# music-thing.net
KiCad netlist of a schematic drawn in EAGLE
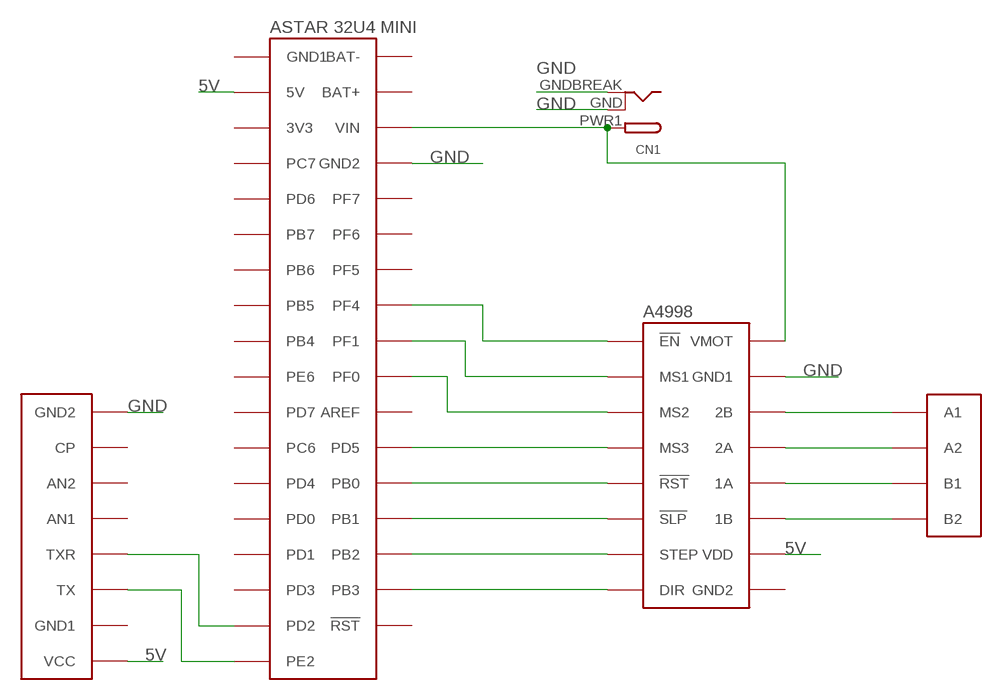
[diagram p0: schematic, sheet 1]

(export (version "E")
  (design (tool "Eeschema 10.0.6"))
  (components
    (comp (ref "CN1")
      (value "DCBARRELSMT")
      (footprint "eagle-import:DCJACK_2MM_SMT")
      (libsource (lib "eagle-import") (part "DCBARRELSMT"))
    )
    (comp (ref "U$1")
      (value "A4998")
      (footprint "eagle-import:A4998")
      (libsource (lib "eagle-import") (part "A4998"))
    )
    (comp (ref "U$2")
      (value "ASTAR32U4MINI")
      (footprint "eagle-import:ASTAR32U4MINI")
      (libsource (lib "eagle-import") (part "ASTAR32U4MINI"))
    )
    (comp (ref "U$3")
      (value "CON-USB-READER-V18")
      (footprint "eagle-import:CON-USB-READER-V18")
      (libsource (lib "eagle-import") (part "CON-USB-READER-V18"))
    )
    (comp (ref "U$4")
      (value "CON-MOTOR")
      (footprint "eagle-import:CON-MOTOR")
      (libsource (lib "eagle-import") (part "CON-MOTOR"))
    )
  )
  (nets
    (net (code "1") (name "/5V") (class "Default")
      (node (ref "U$1") (pin "VDD") (pinfunction "VDD_VDD") (pintype "bidirectional"))
      (node (ref "U$2") (pin "5V") (pinfunction "5V_5V") (pintype "bidirectional"))
      (node (ref "U$3") (pin "VCC") (pinfunction "VCC_VCC") (pintype "bidirectional"))
    )
    (net (code "2") (name "/GND") (class "Default")
      (node (ref "CN1") (pin "GND") (pinfunction "GNDBREAK_GND") (pintype "power_in"))
      (node (ref "CN1") (pin "GNDBREAK") (pinfunction "GND_GNDBREAK") (pintype "power_in"))
      (node (ref "U$1") (pin "GND1") (pinfunction "GND1_GND1") (pintype "bidirectional"))
      (node (ref "U$2") (pin "GND2") (pinfunction "GND2_GND2") (pintype "bidirectional"))
      (node (ref "U$3") (pin "GND2") (pinfunction "GND2_GND2") (pintype "bidirectional"))
    )
    (net (code "3") (name "Net-(CN1-PWR)") (class "Default")
      (node (ref "CN1") (pin "PWR1") (pinfunction "PWR_PWR1") (pintype "power_in"))
      (node (ref "U$1") (pin "VMOT") (pinfunction "VMOT_VMOT") (pintype "bidirectional"))
      (node (ref "U$2") (pin "VIN") (pinfunction "VIN_VIN") (pintype "bidirectional"))
    )
    (net (code "4") (name "Net-(U$1-Pad1A)") (class "Default")
      (node (ref "U$1") (pin "1A") (pinfunction "1A_1A") (pintype "bidirectional"))
      (node (ref "U$4") (pin "B1") (pinfunction "B1_B1") (pintype "bidirectional"))
    )
    (net (code "5") (name "Net-(U$1-Pad1B)") (class "Default")
      (node (ref "U$1") (pin "1B") (pinfunction "1B_1B") (pintype "bidirectional"))
      (node (ref "U$4") (pin "B2") (pinfunction "B2_B2") (pintype "bidirectional"))
    )
    (net (code "6") (name "Net-(U$1-Pad2A)") (class "Default")
      (node (ref "U$1") (pin "2A") (pinfunction "2A_2A") (pintype "bidirectional"))
      (node (ref "U$4") (pin "A2") (pinfunction "A2_A2") (pintype "bidirectional"))
    )
    (net (code "7") (name "Net-(U$1-Pad2B)") (class "Default")
      (node (ref "U$1") (pin "2B") (pinfunction "2B_2B") (pintype "bidirectional"))
      (node (ref "U$4") (pin "A1") (pinfunction "A1_A1") (pintype "bidirectional"))
    )
    (net (code "8") (name "Net-(U$1-PadDIR)") (class "Default")
      (node (ref "U$1") (pin "DIR") (pinfunction "DIR_DIR") (pintype "bidirectional"))
      (node (ref "U$2") (pin "PB3") (pinfunction "PB3_PB3") (pintype "bidirectional"))
    )
    (net (code "9") (name "Net-(U$1-PadMS1)") (class "Default")
      (node (ref "U$1") (pin "MS1") (pinfunction "MS1_MS1") (pintype "bidirectional"))
      (node (ref "U$2") (pin "PF1") (pinfunction "PF1_PF1") (pintype "bidirectional"))
    )
    (net (code "10") (name "Net-(U$1-PadMS2)") (class "Default")
      (node (ref "U$1") (pin "MS2") (pinfunction "MS2_MS2") (pintype "bidirectional"))
      (node (ref "U$2") (pin "PF0") (pinfunction "PF0_PF0") (pintype "bidirectional"))
    )
    (net (code "11") (name "Net-(U$1-PadMS3)") (class "Default")
      (node (ref "U$1") (pin "MS3") (pinfunction "MS3_MS3") (pintype "bidirectional"))
      (node (ref "U$2") (pin "PD5") (pinfunction "PD5_PD5") (pintype "bidirectional"))
    )
    (net (code "12") (name "Net-(U$1-STEP)") (class "Default")
      (node (ref "U$1") (pin "STP") (pinfunction "STEP_STP") (pintype "bidirectional"))
      (node (ref "U$2") (pin "PB2") (pinfunction "PB2_PB2") (pintype "bidirectional"))
    )
    (net (code "13") (name "Net-(U$1-~{EN})") (class "Default")
      (node (ref "U$1") (pin "!EN") (pinfunction "~{EN}_!EN") (pintype "bidirectional"))
      (node (ref "U$2") (pin "PF4") (pinfunction "PF4_PF4") (pintype "bidirectional"))
    )
    (net (code "14") (name "Net-(U$1-~{RST})") (class "Default")
      (node (ref "U$1") (pin "!RST") (pinfunction "~{RST}_!RST") (pintype "bidirectional"))
      (node (ref "U$2") (pin "PB0") (pinfunction "PB0_PB0") (pintype "bidirectional"))
    )
    (net (code "15") (name "Net-(U$1-~{SLP})") (class "Default")
      (node (ref "U$1") (pin "!SLP") (pinfunction "~{SLP}_!SLP") (pintype "bidirectional"))
      (node (ref "U$2") (pin "PB1") (pinfunction "PB1_PB1") (pintype "bidirectional"))
    )
    (net (code "16") (name "Net-(U$2-PadPD2)") (class "Default")
      (node (ref "U$2") (pin "PD2") (pinfunction "PD2_PD2") (pintype "bidirectional"))
      (node (ref "U$3") (pin "TXR") (pinfunction "TXR_TXR") (pintype "bidirectional"))
    )
    (net (code "17") (name "Net-(U$2-PadPE2)") (class "Default")
      (node (ref "U$2") (pin "PE2") (pinfunction "PE2_PE2") (pintype "bidirectional"))
      (node (ref "U$3") (pin "TX") (pinfunction "TX_TX") (pintype "bidirectional"))
    )
    (net (code "18") (name "unconnected-(U$1-PadGND2)") (class "Default")
      (node (ref "U$1") (pin "GND2") (pinfunction "GND2_GND2") (pintype "bidirectional"))
    )
    (net (code "19") (name "unconnected-(U$2-Pad3V3)") (class "Default")
      (node (ref "U$2") (pin "3V3") (pinfunction "3V3_3V3") (pintype "bidirectional"))
    )
    (net (code "20") (name "unconnected-(U$2-PadAREF)") (class "Default")
      (node (ref "U$2") (pin "AREF") (pinfunction "AREF_AREF") (pintype "bidirectional"))
    )
    (net (code "21") (name "unconnected-(U$2-PadBAT+)") (class "Default")
      (node (ref "U$2") (pin "BAT+") (pinfunction "BAT+_BAT+") (pintype "bidirectional"))
    )
    (net (code "22") (name "unconnected-(U$2-PadBAT-)") (class "Default")
      (node (ref "U$2") (pin "BAT-") (pinfunction "BAT-_BAT-") (pintype "bidirectional"))
    )
    (net (code "23") (name "unconnected-(U$2-PadGND1)") (class "Default")
      (node (ref "U$2") (pin "GND1") (pinfunction "GND1_GND1") (pintype "bidirectional"))
    )
    (net (code "24") (name "unconnected-(U$2-PadPB4)") (class "Default")
      (node (ref "U$2") (pin "PB4") (pinfunction "PB4_PB4") (pintype "bidirectional"))
    )
    (net (code "25") (name "unconnected-(U$2-PadPB5)") (class "Default")
      (node (ref "U$2") (pin "PB5") (pinfunction "PB5_PB5") (pintype "bidirectional"))
    )
    (net (code "26") (name "unconnected-(U$2-PadPB6)") (class "Default")
      (node (ref "U$2") (pin "PB6") (pinfunction "PB6_PB6") (pintype "bidirectional"))
    )
    (net (code "27") (name "unconnected-(U$2-PadPB7)") (class "Default")
      (node (ref "U$2") (pin "PB7") (pinfunction "PB7_PB7") (pintype "bidirectional"))
    )
    (net (code "28") (name "unconnected-(U$2-PadPC6)") (class "Default")
      (node (ref "U$2") (pin "PC6") (pinfunction "PC6_PC6") (pintype "bidirectional"))
    )
    (net (code "29") (name "unconnected-(U$2-PadPC7)") (class "Default")
      (node (ref "U$2") (pin "PC7") (pinfunction "PC7_PC7") (pintype "bidirectional"))
    )
    (net (code "30") (name "unconnected-(U$2-PadPD0)") (class "Default")
      (node (ref "U$2") (pin "PD0") (pinfunction "PD0_PD0") (pintype "bidirectional"))
    )
    (net (code "31") (name "unconnected-(U$2-PadPD1)") (class "Default")
      (node (ref "U$2") (pin "PD1") (pinfunction "PD1_PD1") (pintype "bidirectional"))
    )
    (net (code "32") (name "unconnected-(U$2-PadPD3)") (class "Default")
      (node (ref "U$2") (pin "PD3") (pinfunction "PD3_PD3") (pintype "bidirectional"))
    )
    (net (code "33") (name "unconnected-(U$2-PadPD4)") (class "Default")
      (node (ref "U$2") (pin "PD4") (pinfunction "PD4_PD4") (pintype "bidirectional"))
    )
    (net (code "34") (name "unconnected-(U$2-PadPD6)") (class "Default")
      (node (ref "U$2") (pin "PD6") (pinfunction "PD6_PD6") (pintype "bidirectional"))
    )
    (net (code "35") (name "unconnected-(U$2-PadPD7)") (class "Default")
      (node (ref "U$2") (pin "PD7") (pinfunction "PD7_PD7") (pintype "bidirectional"))
    )
    (net (code "36") (name "unconnected-(U$2-PadPE6)") (class "Default")
      (node (ref "U$2") (pin "PE6") (pinfunction "PE6_PE6") (pintype "bidirectional"))
    )
    (net (code "37") (name "unconnected-(U$2-PadPF5)") (class "Default")
      (node (ref "U$2") (pin "PF5") (pinfunction "PF5_PF5") (pintype "bidirectional"))
    )
    (net (code "38") (name "unconnected-(U$2-PadPF6)") (class "Default")
      (node (ref "U$2") (pin "PF6") (pinfunction "PF6_PF6") (pintype "bidirectional"))
    )
    (net (code "39") (name "unconnected-(U$2-PadPF7)") (class "Default")
      (node (ref "U$2") (pin "PF7") (pinfunction "PF7_PF7") (pintype "bidirectional"))
    )
    (net (code "40") (name "unconnected-(U$2-~{RST}-Pad!RST)") (class "Default")
      (node (ref "U$2") (pin "!RST") (pinfunction "~{RST}_!RST") (pintype "bidirectional"))
    )
    (net (code "41") (name "unconnected-(U$3-PadAN1)") (class "Default")
      (node (ref "U$3") (pin "AN1") (pinfunction "AN1_AN1") (pintype "bidirectional"))
    )
    (net (code "42") (name "unconnected-(U$3-PadAN2)") (class "Default")
      (node (ref "U$3") (pin "AN2") (pinfunction "AN2_AN2") (pintype "bidirectional"))
    )
    (net (code "43") (name "unconnected-(U$3-PadCP)") (class "Default")
      (node (ref "U$3") (pin "CP") (pinfunction "CP_CP") (pintype "bidirectional"))
    )
    (net (code "44") (name "unconnected-(U$3-PadGND1)") (class "Default")
      (node (ref "U$3") (pin "GND1") (pinfunction "GND1_GND1") (pintype "bidirectional"))
    )
  )
)
